# 1XGSH00_ANALOG.net
KiCad netlist of a schematic drawn in Altium Designer
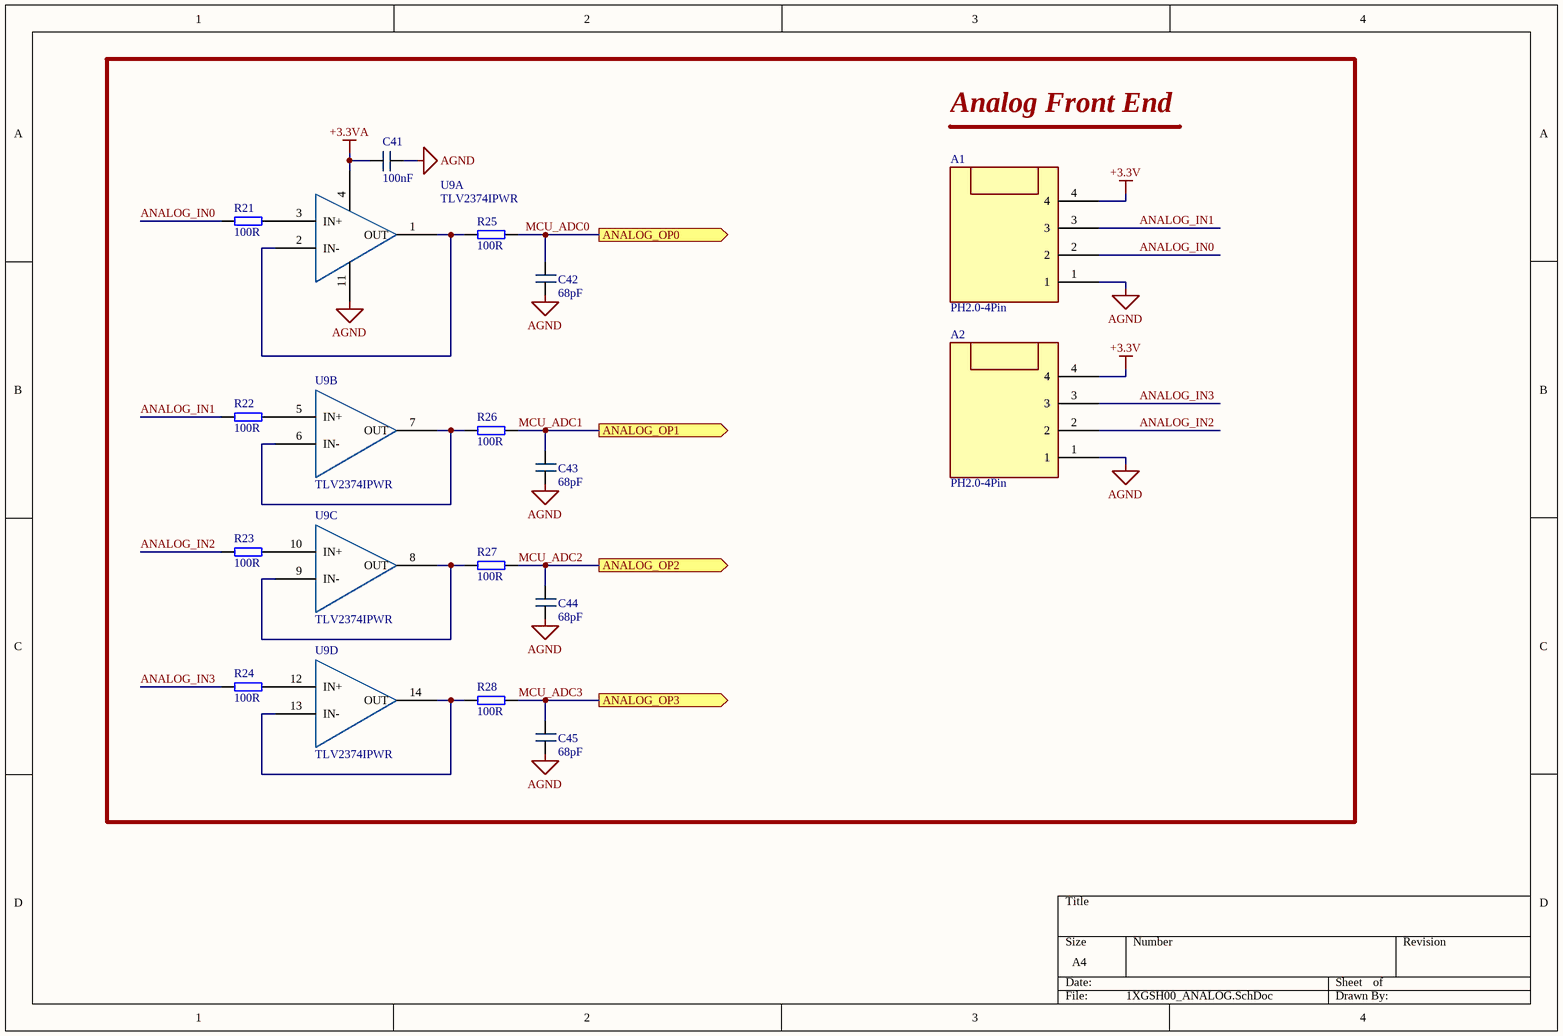
[diagram p0: 1XGSH00_ANALOG.SchDoc]

(export (version "E")
  (design (tool "Eeschema 10.0.6"))
  (components
    (comp (ref "A1")
      (value "PH2.0-4Pin")
      (footprint "X1251WRS-04HF-LPSW")
      (libsource (lib "LGG21") (part "PH2.0-4Pin"))
    )
    (comp (ref "A2")
      (value "PH2.0-4Pin")
      (footprint "X1251WRS-04HF-LPSW")
      (libsource (lib "LGG21") (part "PH2.0-4Pin"))
    )
    (comp (ref "C41")
      (value "100nF")
      (footprint "0402_C")
      (description "Capacitor")
      (libsource (lib "LGG21") (part "Capacitor"))
    )
    (comp (ref "C42")
      (value "68pF")
      (footprint "0402_C")
      (description "Capacitor")
      (libsource (lib "LGG21") (part "Capacitor"))
    )
    (comp (ref "C43")
      (value "68pF")
      (footprint "0402_C")
      (description "Capacitor")
      (libsource (lib "LGG21") (part "Capacitor"))
    )
    (comp (ref "C44")
      (value "68pF")
      (footprint "0402_C")
      (description "Capacitor")
      (libsource (lib "LGG21") (part "Capacitor"))
    )
    (comp (ref "C45")
      (value "68pF")
      (footprint "0402_C")
      (description "Capacitor")
      (libsource (lib "LGG21") (part "Capacitor"))
    )
    (comp (ref "R21")
      (value "100R")
      (footprint "0402_R")
      (description "Resistor")
      (libsource (lib "LGG21") (part "Resistor"))
    )
    (comp (ref "R22")
      (value "100R")
      (footprint "0402_R")
      (description "Resistor")
      (libsource (lib "LGG21") (part "Resistor"))
    )
    (comp (ref "R23")
      (value "100R")
      (footprint "0402_R")
      (description "Resistor")
      (libsource (lib "LGG21") (part "Resistor"))
    )
    (comp (ref "R24")
      (value "100R")
      (footprint "0402_R")
      (description "Resistor")
      (libsource (lib "LGG21") (part "Resistor"))
    )
    (comp (ref "R25")
      (value "100R")
      (footprint "0402_R")
      (description "Resistor")
      (libsource (lib "LGG21") (part "Resistor"))
    )
    (comp (ref "R26")
      (value "100R")
      (footprint "0402_R")
      (description "Resistor")
      (libsource (lib "LGG21") (part "Resistor"))
    )
    (comp (ref "R27")
      (value "100R")
      (footprint "0402_R")
      (description "Resistor")
      (libsource (lib "LGG21") (part "Resistor"))
    )
    (comp (ref "R28")
      (value "100R")
      (footprint "0402_R")
      (description "Resistor")
      (libsource (lib "LGG21") (part "Resistor"))
    )
    (comp (ref "U9")
      (value "TLV2374IPWR")
      (footprint "TSSOP-14")
      (description "4 Channels OPAMP")
      (libsource (lib "LGG21") (part "TLV2374IPWR"))
    )
  )
  (nets
    (net (code "1") (name "+3.3V") (class "Default")
      (node (ref "A1") (pin "4") (pinfunction "4_4") (pintype "passive"))
      (node (ref "A2") (pin "4") (pinfunction "4_4") (pintype "passive"))
    )
    (net (code "2") (name "+3.3VA") (class "Default")
      (node (ref "C41") (pin "1") (pinfunction "-_1") (pintype "passive"))
      (node (ref "U9") (pin "4") (pinfunction "VDD_4") (pintype "passive"))
    )
    (net (code "3") (name "/ANALOG_IN0") (class "Default")
      (node (ref "A1") (pin "2") (pinfunction "2_2") (pintype "passive"))
      (node (ref "R21") (pin "1") (pinfunction "1_1") (pintype "passive"))
    )
    (net (code "4") (name "/ANALOG_IN1") (class "Default")
      (node (ref "A1") (pin "3") (pinfunction "3_3") (pintype "passive"))
      (node (ref "R22") (pin "1") (pinfunction "1_1") (pintype "passive"))
    )
    (net (code "5") (name "/ANALOG_IN2") (class "Default")
      (node (ref "A2") (pin "2") (pinfunction "2_2") (pintype "passive"))
      (node (ref "R23") (pin "1") (pinfunction "1_1") (pintype "passive"))
    )
    (net (code "6") (name "/ANALOG_IN3") (class "Default")
      (node (ref "A2") (pin "3") (pinfunction "3_3") (pintype "passive"))
      (node (ref "R24") (pin "1") (pinfunction "1_1") (pintype "passive"))
    )
    (net (code "7") (name "/MCU_ADC0") (class "Default")
      (node (ref "C42") (pin "2") (pinfunction "-_2") (pintype "passive"))
      (node (ref "R25") (pin "2") (pinfunction "2_2") (pintype "passive"))
    )
    (net (code "8") (name "/MCU_ADC1") (class "Default")
      (node (ref "C43") (pin "2") (pinfunction "-_2") (pintype "passive"))
      (node (ref "R26") (pin "2") (pinfunction "2_2") (pintype "passive"))
    )
    (net (code "9") (name "/MCU_ADC2") (class "Default")
      (node (ref "C44") (pin "2") (pinfunction "-_2") (pintype "passive"))
      (node (ref "R27") (pin "2") (pinfunction "2_2") (pintype "passive"))
    )
    (net (code "10") (name "/MCU_ADC3") (class "Default")
      (node (ref "C45") (pin "2") (pinfunction "-_2") (pintype "passive"))
      (node (ref "R28") (pin "2") (pinfunction "2_2") (pintype "passive"))
    )
    (net (code "11") (name "AGND") (class "Default")
      (node (ref "A1") (pin "1") (pinfunction "1_1") (pintype "passive"))
      (node (ref "A2") (pin "1") (pinfunction "1_1") (pintype "passive"))
      (node (ref "C41") (pin "2") (pinfunction "-_2") (pintype "passive"))
      (node (ref "C42") (pin "1") (pinfunction "-_1") (pintype "passive"))
      (node (ref "C43") (pin "1") (pinfunction "-_1") (pintype "passive"))
      (node (ref "C44") (pin "1") (pinfunction "-_1") (pintype "passive"))
      (node (ref "C45") (pin "1") (pinfunction "-_1") (pintype "passive"))
      (node (ref "U9") (pin "11") (pinfunction "GND_11") (pintype "passive"))
    )
    (net (code "12") (name "Net-(U9A-IN+)") (class "Default")
      (node (ref "R21") (pin "2") (pinfunction "2_2") (pintype "passive"))
      (node (ref "U9") (pin "3") (pinfunction "IN+_3") (pintype "passive"))
    )
    (net (code "13") (name "Net-(U9A-IN-)") (class "Default")
      (node (ref "R25") (pin "1") (pinfunction "1_1") (pintype "passive"))
      (node (ref "U9") (pin "1") (pinfunction "OUT_1") (pintype "passive"))
      (node (ref "U9") (pin "2") (pinfunction "IN-_2") (pintype "passive"))
    )
    (net (code "14") (name "Net-(U9B-IN+)") (class "Default")
      (node (ref "R22") (pin "2") (pinfunction "2_2") (pintype "passive"))
      (node (ref "U9") (pin "5") (pinfunction "IN+_5") (pintype "passive"))
    )
    (net (code "15") (name "Net-(U9B-IN-)") (class "Default")
      (node (ref "R26") (pin "1") (pinfunction "1_1") (pintype "passive"))
      (node (ref "U9") (pin "6") (pinfunction "IN-_6") (pintype "passive"))
      (node (ref "U9") (pin "7") (pinfunction "OUT_7") (pintype "passive"))
    )
    (net (code "16") (name "Net-(U9C-IN+)") (class "Default")
      (node (ref "R23") (pin "2") (pinfunction "2_2") (pintype "passive"))
      (node (ref "U9") (pin "10") (pinfunction "IN+_10") (pintype "passive"))
    )
    (net (code "17") (name "Net-(U9C-IN-)") (class "Default")
      (node (ref "R27") (pin "1") (pinfunction "1_1") (pintype "passive"))
      (node (ref "U9") (pin "8") (pinfunction "OUT_8") (pintype "passive"))
      (node (ref "U9") (pin "9") (pinfunction "IN-_9") (pintype "passive"))
    )
    (net (code "18") (name "Net-(U9D-IN+)") (class "Default")
      (node (ref "R24") (pin "2") (pinfunction "2_2") (pintype "passive"))
      (node (ref "U9") (pin "12") (pinfunction "IN+_12") (pintype "passive"))
    )
    (net (code "19") (name "Net-(U9D-IN-)") (class "Default")
      (node (ref "R28") (pin "1") (pinfunction "1_1") (pintype "passive"))
      (node (ref "U9") (pin "13") (pinfunction "IN-_13") (pintype "passive"))
      (node (ref "U9") (pin "14") (pinfunction "OUT_14") (pintype "passive"))
    )
  )
)
